# power.net
KiCad netlist of a schematic drawn in Altium Designer
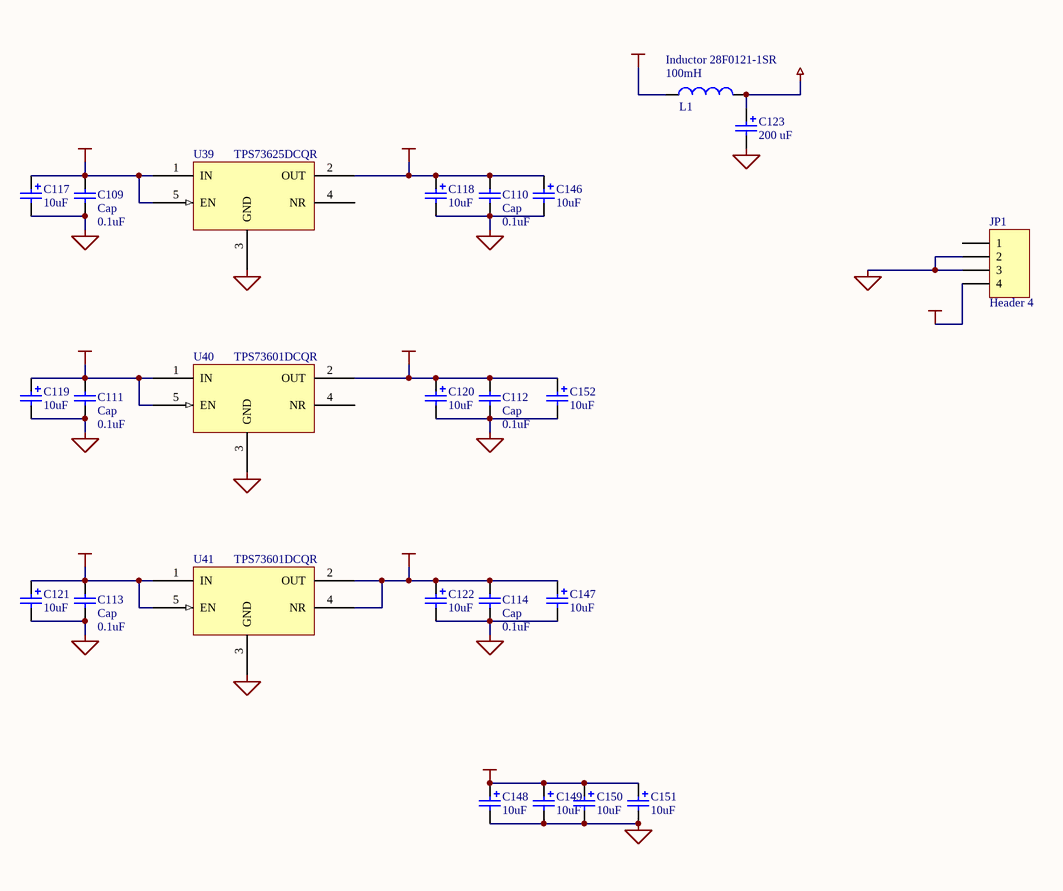
[diagram p0: power.SCHDOC]

(export (version "E")
  (design (tool "Eeschema 10.0.6"))
  (components
    (comp (ref "C109")
      (value "Cap")
      (footprint "CC1608-0603")
      (description "Capacitor")
      (fields
        (field (name "MANUFACTURER") "Generic Components")
        (field (name "ALTIUM_VALUE") "0.1uF")
        (field (name "PUBLISHER") "Altium Limited")
      )
      (libsource (lib "Miscellaneous Devices") (part "Cap"))
    )
    (comp (ref "C110")
      (value "Cap")
      (footprint "CC1608-0603")
      (description "Capacitor")
      (fields
        (field (name "MANUFACTURER") "Generic Components")
        (field (name "ALTIUM_VALUE") "0.1uF")
        (field (name "PUBLISHER") "Altium Limited")
      )
      (libsource (lib "Miscellaneous Devices") (part "Cap"))
    )
    (comp (ref "C111")
      (value "Cap")
      (footprint "CC1608-0603")
      (description "Capacitor")
      (fields
        (field (name "MANUFACTURER") "Generic Components")
        (field (name "ALTIUM_VALUE") "0.1uF")
        (field (name "PUBLISHER") "Altium Limited")
      )
      (libsource (lib "Miscellaneous Devices") (part "Cap"))
    )
    (comp (ref "C112")
      (value "Cap")
      (footprint "CC1608-0603")
      (description "Capacitor")
      (fields
        (field (name "MANUFACTURER") "Generic Components")
        (field (name "ALTIUM_VALUE") "0.1uF")
        (field (name "PUBLISHER") "Altium Limited")
      )
      (libsource (lib "Miscellaneous Devices") (part "Cap"))
    )
    (comp (ref "C113")
      (value "Cap")
      (footprint "CC1608-0603")
      (description "Capacitor")
      (fields
        (field (name "MANUFACTURER") "Generic Components")
        (field (name "ALTIUM_VALUE") "0.1uF")
        (field (name "PUBLISHER") "Altium Limited")
      )
      (libsource (lib "Miscellaneous Devices") (part "Cap"))
    )
    (comp (ref "C114")
      (value "Cap")
      (footprint "CC1608-0603")
      (description "Capacitor")
      (fields
        (field (name "MANUFACTURER") "Generic Components")
        (field (name "ALTIUM_VALUE") "0.1uF")
        (field (name "PUBLISHER") "Altium Limited")
      )
      (libsource (lib "Miscellaneous Devices") (part "Cap"))
    )
    (comp (ref "C117")
      (value "Cap Pol1")
      (footprint "TC7343-2917")
      (description "Polarized Capacitor (Radial)")
      (fields
        (field (name "MANUFACTURER") "Generic Components")
        (field (name "ALTIUM_VALUE") "10uF")
        (field (name "PUBLISHER") "Altium Limited")
      )
      (libsource (lib "Miscellaneous Devices") (part "Cap Pol1"))
    )
    (comp (ref "C118")
      (value "Cap Pol1")
      (footprint "TC7343-2917")
      (description "Polarized Capacitor (Radial)")
      (fields
        (field (name "MANUFACTURER") "Generic Components")
        (field (name "ALTIUM_VALUE") "10uF")
        (field (name "PUBLISHER") "Altium Limited")
      )
      (libsource (lib "Miscellaneous Devices") (part "Cap Pol1"))
    )
    (comp (ref "C119")
      (value "Cap Pol1")
      (footprint "TC7343-2917")
      (description "Polarized Capacitor (Radial)")
      (fields
        (field (name "MANUFACTURER") "Generic Components")
        (field (name "ALTIUM_VALUE") "10uF")
        (field (name "PUBLISHER") "Altium Limited")
      )
      (libsource (lib "Miscellaneous Devices") (part "Cap Pol1"))
    )
    (comp (ref "C120")
      (value "Cap Pol1")
      (footprint "TC7343-2917")
      (description "Polarized Capacitor (Radial)")
      (fields
        (field (name "MANUFACTURER") "Generic Components")
        (field (name "ALTIUM_VALUE") "10uF")
        (field (name "PUBLISHER") "Altium Limited")
      )
      (libsource (lib "Miscellaneous Devices") (part "Cap Pol1"))
    )
    (comp (ref "C121")
      (value "Cap Pol1")
      (footprint "TC7343-2917")
      (description "Polarized Capacitor (Radial)")
      (fields
        (field (name "MANUFACTURER") "Generic Components")
        (field (name "ALTIUM_VALUE") "10uF")
        (field (name "PUBLISHER") "Altium Limited")
      )
      (libsource (lib "Miscellaneous Devices") (part "Cap Pol1"))
    )
    (comp (ref "C122")
      (value "Cap Pol1")
      (footprint "TC7343-2917")
      (description "Polarized Capacitor (Radial)")
      (fields
        (field (name "MANUFACTURER") "Generic Components")
        (field (name "ALTIUM_VALUE") "10uF")
        (field (name "PUBLISHER") "Altium Limited")
      )
      (libsource (lib "Miscellaneous Devices") (part "Cap Pol1"))
    )
    (comp (ref "C123")
      (value "200 uF")
      (footprint "PanasonicE")
      (description "Polarized Capacitor (Surface Mount)")
      (fields (field (name "MANUFACTURER") "Generic Components") (field (name "PUBLISHER") "Altium Limited"))
      (libsource (lib "Miscellaneous Devices") (part "Cap Pol3"))
    )
    (comp (ref "C146")
      (value "Cap Pol1")
      (footprint "TC7343-2917")
      (description "Polarized Capacitor (Radial)")
      (fields
        (field (name "MANUFACTURER") "Generic Components")
        (field (name "ALTIUM_VALUE") "10uF")
        (field (name "PUBLISHER") "Altium Limited")
      )
      (libsource (lib "Miscellaneous Devices") (part "Cap Pol1"))
    )
    (comp (ref "C147")
      (value "Cap Pol1")
      (footprint "TC7343-2917")
      (description "Polarized Capacitor (Radial)")
      (fields
        (field (name "MANUFACTURER") "Generic Components")
        (field (name "ALTIUM_VALUE") "10uF")
        (field (name "PUBLISHER") "Altium Limited")
      )
      (libsource (lib "Miscellaneous Devices") (part "Cap Pol1"))
    )
    (comp (ref "C148")
      (value "Cap Pol1")
      (footprint "TC7343-2917")
      (description "Polarized Capacitor (Radial)")
      (fields
        (field (name "MANUFACTURER") "Generic Components")
        (field (name "ALTIUM_VALUE") "10uF")
        (field (name "PUBLISHER") "Altium Limited")
      )
      (libsource (lib "Miscellaneous Devices") (part "Cap Pol1"))
    )
    (comp (ref "C149")
      (value "Cap Pol1")
      (footprint "TC7343-2917")
      (description "Polarized Capacitor (Radial)")
      (fields
        (field (name "MANUFACTURER") "Generic Components")
        (field (name "ALTIUM_VALUE") "10uF")
        (field (name "PUBLISHER") "Altium Limited")
      )
      (libsource (lib "Miscellaneous Devices") (part "Cap Pol1"))
    )
    (comp (ref "C150")
      (value "Cap Pol1")
      (footprint "TC7343-2917")
      (description "Polarized Capacitor (Radial)")
      (fields
        (field (name "MANUFACTURER") "Generic Components")
        (field (name "ALTIUM_VALUE") "10uF")
        (field (name "PUBLISHER") "Altium Limited")
      )
      (libsource (lib "Miscellaneous Devices") (part "Cap Pol1"))
    )
    (comp (ref "C151")
      (value "Cap Pol1")
      (footprint "TC7343-2917")
      (description "Polarized Capacitor (Radial)")
      (fields
        (field (name "MANUFACTURER") "Generic Components")
        (field (name "ALTIUM_VALUE") "10uF")
        (field (name "PUBLISHER") "Altium Limited")
      )
      (libsource (lib "Miscellaneous Devices") (part "Cap Pol1"))
    )
    (comp (ref "C152")
      (value "Cap Pol1")
      (footprint "TC7343-2917")
      (description "Polarized Capacitor (Radial)")
      (fields
        (field (name "MANUFACTURER") "Generic Components")
        (field (name "ALTIUM_VALUE") "10uF")
        (field (name "PUBLISHER") "Altium Limited")
      )
      (libsource (lib "Miscellaneous Devices") (part "Cap Pol1"))
    )
    (comp (ref "JP1")
      (value "Header 4")
      (footprint "PCHW-molex")
      (description "Header, 4-Pin")
      (fields (field (name "MANUFACTURER") "Generic Components") (field (name "PUBLISHER") "Altium Limited"))
      (libsource (lib "Miscellaneous Connectors") (part "Header 4"))
    )
    (comp (ref "L1")
      (value "Inductor 28F0121-1SR")
      (footprint "STEWARD_1SR")
      (description "Inductor")
      (fields
        (field (name "MANUFACTURER") "Generic Components")
        (field (name "ALTIUM_VALUE") "100mH")
        (field (name "PUBLISHER") "Altium Limited")
      )
      (libsource (lib "Miscellaneous Devices") (part "Inductor"))
    )
    (comp (ref "U39")
      (value "TPS73625DCQR")
      (footprint "SOT223-5/Simple")
      (description "Cap-free NMOS 400 mA LDO")
      (libsource (lib "My devices") (part "TPS736XX"))
    )
    (comp (ref "U40")
      (value "TPS73601DCQR")
      (footprint "SOT223-5/Simple")
      (description "Cap-free NMOS 400 mA LDO")
      (libsource (lib "My devices") (part "TPS736XX"))
    )
    (comp (ref "U41")
      (value "TPS73601DCQR")
      (footprint "SOT223-5/Simple")
      (description "Cap-free NMOS 400 mA LDO")
      (libsource (lib "My devices") (part "TPS736XX"))
    )
  )
  (nets
    (net (code "1") (name "+1.2VCC") (class "Default")
      (node (ref "C114") (pin "2") (pinfunction "2_2") (pintype "passive"))
      (node (ref "C122") (pin "1") (pinfunction "1_1") (pintype "passive"))
      (node (ref "C147") (pin "1") (pinfunction "1_1") (pintype "passive"))
      (node (ref "U41") (pin "2") (pinfunction "OUT_2") (pintype "power_in"))
      (node (ref "U41") (pin "4") (pinfunction "NR_4") (pintype "passive"))
    )
    (net (code "2") (name "+1.2VCCUSB") (class "Default")
      (node (ref "C112") (pin "2") (pinfunction "2_2") (pintype "passive"))
      (node (ref "C120") (pin "1") (pinfunction "1_1") (pintype "passive"))
      (node (ref "C152") (pin "1") (pinfunction "1_1") (pintype "passive"))
      (node (ref "U40") (pin "2") (pinfunction "OUT_2") (pintype "power_in"))
    )
    (net (code "3") (name "+2.5VCC") (class "Default")
      (node (ref "C110") (pin "2") (pinfunction "2_2") (pintype "passive"))
      (node (ref "C118") (pin "1") (pinfunction "1_1") (pintype "passive"))
      (node (ref "C146") (pin "1") (pinfunction "1_1") (pintype "passive"))
      (node (ref "U39") (pin "2") (pinfunction "OUT_2") (pintype "power_in"))
    )
    (net (code "4") (name "+5VCC") (class "Default")
      (node (ref "JP1") (pin "4") (pinfunction "4_4") (pintype "passive"))
      (node (ref "L1") (pin "1") (pinfunction "1_1") (pintype "passive"))
    )
    (net (code "5") (name "AVDD") (class "Default")
      (node (ref "C123") (pin "1") (pinfunction "1_1") (pintype "passive"))
      (node (ref "L1") (pin "2") (pinfunction "2_2") (pintype "passive"))
    )
    (net (code "6") (name "GND") (class "Default")
      (node (ref "C109") (pin "1") (pinfunction "1_1") (pintype "passive"))
      (node (ref "C110") (pin "1") (pinfunction "1_1") (pintype "passive"))
      (node (ref "C111") (pin "1") (pinfunction "1_1") (pintype "passive"))
      (node (ref "C112") (pin "1") (pinfunction "1_1") (pintype "passive"))
      (node (ref "C113") (pin "1") (pinfunction "1_1") (pintype "passive"))
      (node (ref "C114") (pin "1") (pinfunction "1_1") (pintype "passive"))
      (node (ref "C117") (pin "2") (pinfunction "2_2") (pintype "passive"))
      (node (ref "C118") (pin "2") (pinfunction "2_2") (pintype "passive"))
      (node (ref "C119") (pin "2") (pinfunction "2_2") (pintype "passive"))
      (node (ref "C120") (pin "2") (pinfunction "2_2") (pintype "passive"))
      (node (ref "C121") (pin "2") (pinfunction "2_2") (pintype "passive"))
      (node (ref "C122") (pin "2") (pinfunction "2_2") (pintype "passive"))
      (node (ref "C123") (pin "2") (pinfunction "2_2") (pintype "passive"))
      (node (ref "C146") (pin "2") (pinfunction "2_2") (pintype "passive"))
      (node (ref "C147") (pin "2") (pinfunction "2_2") (pintype "passive"))
      (node (ref "C148") (pin "2") (pinfunction "2_2") (pintype "passive"))
      (node (ref "C149") (pin "2") (pinfunction "2_2") (pintype "passive"))
      (node (ref "C150") (pin "2") (pinfunction "2_2") (pintype "passive"))
      (node (ref "C151") (pin "2") (pinfunction "2_2") (pintype "passive"))
      (node (ref "C152") (pin "2") (pinfunction "2_2") (pintype "passive"))
      (node (ref "JP1") (pin "2") (pinfunction "2_2") (pintype "passive"))
      (node (ref "JP1") (pin "3") (pinfunction "3_3") (pintype "passive"))
      (node (ref "U39") (pin "3") (pinfunction "GND_3") (pintype "power_in"))
      (node (ref "U40") (pin "3") (pinfunction "GND_3") (pintype "power_in"))
      (node (ref "U41") (pin "3") (pinfunction "GND_3") (pintype "power_in"))
    )
    (net (code "7") (name "VCC") (class "Default")
      (node (ref "C109") (pin "2") (pinfunction "2_2") (pintype "passive"))
      (node (ref "C111") (pin "2") (pinfunction "2_2") (pintype "passive"))
      (node (ref "C113") (pin "2") (pinfunction "2_2") (pintype "passive"))
      (node (ref "C117") (pin "1") (pinfunction "1_1") (pintype "passive"))
      (node (ref "C119") (pin "1") (pinfunction "1_1") (pintype "passive"))
      (node (ref "C121") (pin "1") (pinfunction "1_1") (pintype "passive"))
      (node (ref "C148") (pin "1") (pinfunction "1_1") (pintype "passive"))
      (node (ref "C149") (pin "1") (pinfunction "1_1") (pintype "passive"))
      (node (ref "C150") (pin "1") (pinfunction "1_1") (pintype "passive"))
      (node (ref "C151") (pin "1") (pinfunction "1_1") (pintype "passive"))
      (node (ref "U39") (pin "1") (pinfunction "IN_1") (pintype "power_in"))
      (node (ref "U39") (pin "5") (pinfunction "EN_5") (pintype "input"))
      (node (ref "U40") (pin "1") (pinfunction "IN_1") (pintype "power_in"))
      (node (ref "U40") (pin "5") (pinfunction "EN_5") (pintype "input"))
      (node (ref "U41") (pin "1") (pinfunction "IN_1") (pintype "power_in"))
      (node (ref "U41") (pin "5") (pinfunction "EN_5") (pintype "input"))
    )
    (net (code "8") (name "unconnected-(JP1-Pad1)") (class "Default")
      (node (ref "JP1") (pin "1") (pinfunction "1_1") (pintype "passive"))
    )
    (net (code "9") (name "unconnected-(U39-NR-Pad4)") (class "Default")
      (node (ref "U39") (pin "4") (pinfunction "NR_4") (pintype "passive"))
    )
    (net (code "10") (name "unconnected-(U40-NR-Pad4)") (class "Default")
      (node (ref "U40") (pin "4") (pinfunction "NR_4") (pintype "passive"))
    )
  )
)
